# RS485_v1.net
KiCad netlist of a schematic drawn in EAGLE
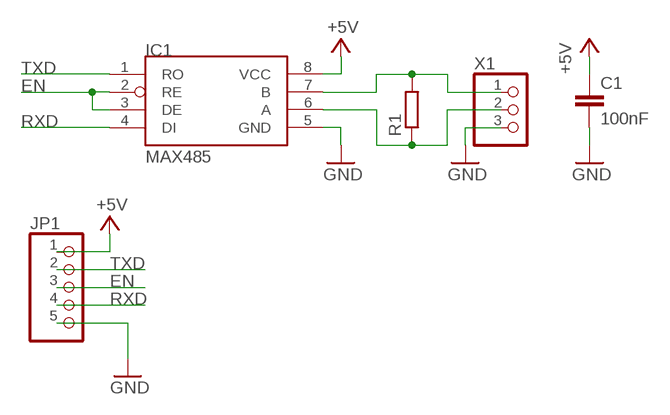
[diagram p0: schematic, sheet 1]

(export (version "E")
  (design (tool "Eeschema 10.0.6"))
  (components
    (comp (ref "C1")
      (value "100nF")
      (footprint "eagle-import:C0805K")
      (libsource (lib "eagle-import") (part "C-EUC0805K"))
    )
    (comp (ref "IC1")
      (value "MAX485")
      (footprint "eagle-import:SO08")
      (libsource (lib "eagle-import") (part "MAX485"))
    )
    (comp (ref "JP1")
      (value "PINHD-1X5")
      (footprint "eagle-import:1X05")
      (libsource (lib "eagle-import") (part "PINHD-1X5"))
    )
    (comp (ref "R1")
      (value "R-EU_R0805")
      (footprint "eagle-import:R0805")
      (libsource (lib "eagle-import") (part "R-EU_R0805"))
    )
    (comp (ref "X1")
      (value "W237-103")
      (footprint "eagle-import:W237-103")
      (libsource (lib "eagle-import") (part "W237-103"))
    )
  )
  (nets
    (net (code "1") (name "+5V") (class "Default")
      (node (ref "C1") (pin "1") (pinfunction "1_1") (pintype "passive"))
      (node (ref "IC1") (pin "8") (pinfunction "VCC_8") (pintype "bidirectional"))
      (node (ref "JP1") (pin "1") (pinfunction "1_1") (pintype "passive"))
    )
    (net (code "2") (name "/EN") (class "Default")
      (node (ref "IC1") (pin "2") (pinfunction "RE_2") (pintype "bidirectional"))
      (node (ref "IC1") (pin "3") (pinfunction "DE_3") (pintype "bidirectional"))
      (node (ref "JP1") (pin "3") (pinfunction "3_3") (pintype "passive"))
    )
    (net (code "3") (name "/RXD") (class "Default")
      (node (ref "IC1") (pin "4") (pinfunction "DI_4") (pintype "bidirectional"))
      (node (ref "JP1") (pin "4") (pinfunction "4_4") (pintype "passive"))
    )
    (net (code "4") (name "/TXD") (class "Default")
      (node (ref "IC1") (pin "1") (pinfunction "RO_1") (pintype "bidirectional"))
      (node (ref "JP1") (pin "2") (pinfunction "2_2") (pintype "passive"))
    )
    (net (code "5") (name "GND") (class "Default")
      (node (ref "C1") (pin "2") (pinfunction "2_2") (pintype "passive"))
      (node (ref "IC1") (pin "5") (pinfunction "GND_5") (pintype "bidirectional"))
      (node (ref "JP1") (pin "5") (pinfunction "5_5") (pintype "passive"))
      (node (ref "X1") (pin "3") (pinfunction "3_3") (pintype "passive"))
    )
    (net (code "6") (name "Net-(IC1-A)") (class "Default")
      (node (ref "IC1") (pin "6") (pinfunction "A_6") (pintype "bidirectional"))
      (node (ref "R1") (pin "1") (pinfunction "1_1") (pintype "passive"))
      (node (ref "X1") (pin "2") (pinfunction "2_2") (pintype "passive"))
    )
    (net (code "7") (name "Net-(IC1-B)") (class "Default")
      (node (ref "IC1") (pin "7") (pinfunction "B_7") (pintype "bidirectional"))
      (node (ref "R1") (pin "2") (pinfunction "2_2") (pintype "passive"))
      (node (ref "X1") (pin "1") (pinfunction "1_1") (pintype "passive"))
    )
  )
)
